# Relays.net
KiCad netlist of a schematic drawn in Altium Designer
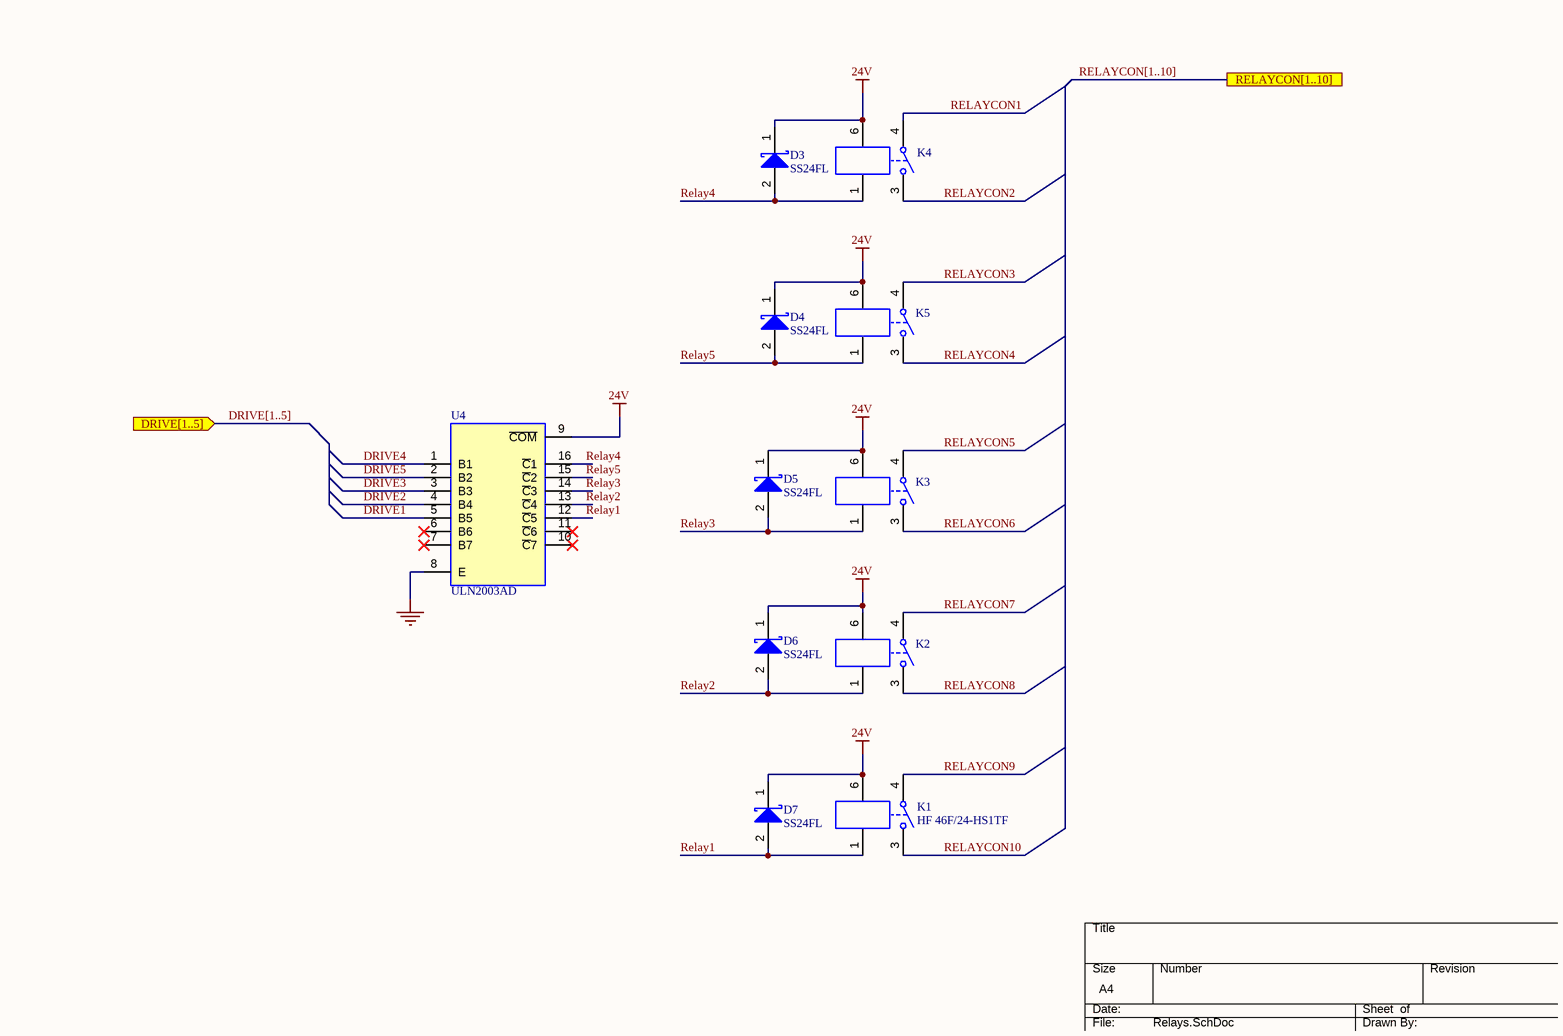
[diagram p0: Relays.SchDoc]

(export (version "E")
  (design (tool "Eeschema 10.0.6"))
  (components
    (comp (ref "D3")
      (value "SS24FL")
      (footprint "SOD-123F")
      (fields (field (name "PART NUMBER") "DIS-000000002"))
      (libsource (lib "CMA") (part "DSchottky"))
    )
    (comp (ref "D4")
      (value "SS24FL")
      (footprint "SOD-123F")
      (fields (field (name "PART NUMBER") "DIS-000000002"))
      (libsource (lib "CMA") (part "DSchottky"))
    )
    (comp (ref "D5")
      (value "SS24FL")
      (footprint "SOD-123F")
      (fields (field (name "PART NUMBER") "DIS-000000002"))
      (libsource (lib "CMA") (part "DSchottky"))
    )
    (comp (ref "D6")
      (value "SS24FL")
      (footprint "SOD-123F")
      (fields (field (name "PART NUMBER") "DIS-000000002"))
      (libsource (lib "CMA") (part "DSchottky"))
    )
    (comp (ref "D7")
      (value "SS24FL")
      (footprint "SOD-123F")
      (fields (field (name "PART NUMBER") "DIS-000000002"))
      (libsource (lib "CMA") (part "DSchottky"))
    )
    (comp (ref "K1")
      (value "HF 46F/24-HS1TF")
      (footprint "G6BU-1114P")
      (fields (field (name "PART NUMBER") "RLY-000000002"))
      (libsource (lib "CMA") (part "G6BU-1114P"))
    )
    (comp (ref "K2")
      (value "HF 46F/24-HS1TF")
      (footprint "G6BU-1114P")
      (fields (field (name "PART NUMBER") "RLY-000000002"))
      (libsource (lib "CMA") (part "G6BU-1114P"))
    )
    (comp (ref "K3")
      (value "HF 46F/24-HS1TF")
      (footprint "G6BU-1114P")
      (fields (field (name "PART NUMBER") "RLY-000000002"))
      (libsource (lib "CMA") (part "G6BU-1114P"))
    )
    (comp (ref "K4")
      (value "HF 46F/24-HS1TF")
      (footprint "G6BU-1114P")
      (fields (field (name "PART NUMBER") "RLY-000000002"))
      (libsource (lib "CMA") (part "G6BU-1114P"))
    )
    (comp (ref "K5")
      (value "HF 46F/24-HS1TF")
      (footprint "G6BU-1114P")
      (fields (field (name "PART NUMBER") "RLY-000000002"))
      (libsource (lib "CMA") (part "G6BU-1114P"))
    )
    (comp (ref "U4")
      (value "ULN2003AD")
      (footprint "SOIC-16")
      (fields (field (name "PART NUMBER") "ICD-000000003"))
      (libsource (lib "CMA") (part "ULN2003AD"))
    )
  )
  (nets
    (net (code "1") (name "/DRIVE1") (class "Default")
      (node (ref "U4") (pin "5") (pinfunction "B5_5") (pintype "passive"))
    )
    (net (code "2") (name "/DRIVE2") (class "Default")
      (node (ref "U4") (pin "4") (pinfunction "B4_4") (pintype "passive"))
    )
    (net (code "3") (name "/DRIVE3") (class "Default")
      (node (ref "U4") (pin "3") (pinfunction "B3_3") (pintype "passive"))
    )
    (net (code "4") (name "/DRIVE4") (class "Default")
      (node (ref "U4") (pin "1") (pinfunction "B1_1") (pintype "passive"))
    )
    (net (code "5") (name "/DRIVE5") (class "Default")
      (node (ref "U4") (pin "2") (pinfunction "B2_2") (pintype "passive"))
    )
    (net (code "7") (name "/RELAYCON1") (class "Default")
      (node (ref "K4") (pin "4") (pinfunction "4_4") (pintype "passive"))
    )
    (net (code "8") (name "/RELAYCON2") (class "Default")
      (node (ref "K4") (pin "3") (pinfunction "3_3") (pintype "passive"))
    )
    (net (code "9") (name "/RELAYCON3") (class "Default")
      (node (ref "K5") (pin "4") (pinfunction "4_4") (pintype "passive"))
    )
    (net (code "10") (name "/RELAYCON4") (class "Default")
      (node (ref "K5") (pin "3") (pinfunction "3_3") (pintype "passive"))
    )
    (net (code "11") (name "/RELAYCON5") (class "Default")
      (node (ref "K3") (pin "4") (pinfunction "4_4") (pintype "passive"))
    )
    (net (code "12") (name "/RELAYCON6") (class "Default")
      (node (ref "K3") (pin "3") (pinfunction "3_3") (pintype "passive"))
    )
    (net (code "13") (name "/RELAYCON7") (class "Default")
      (node (ref "K2") (pin "4") (pinfunction "4_4") (pintype "passive"))
    )
    (net (code "14") (name "/RELAYCON8") (class "Default")
      (node (ref "K2") (pin "3") (pinfunction "3_3") (pintype "passive"))
    )
    (net (code "15") (name "/RELAYCON9") (class "Default")
      (node (ref "K1") (pin "4") (pinfunction "4_4") (pintype "passive"))
    )
    (net (code "16") (name "/RELAYCON10") (class "Default")
      (node (ref "K1") (pin "3") (pinfunction "3_3") (pintype "passive"))
    )
    (net (code "18") (name "/Relay1") (class "Default")
      (node (ref "D7") (pin "2") (pinfunction "A_2") (pintype "passive"))
      (node (ref "K1") (pin "1") (pinfunction "1_1") (pintype "passive"))
      (node (ref "U4") (pin "12") (pinfunction "~{C}5_12") (pintype "open_collector"))
    )
    (net (code "19") (name "/Relay2") (class "Default")
      (node (ref "D6") (pin "2") (pinfunction "A_2") (pintype "passive"))
      (node (ref "K2") (pin "1") (pinfunction "1_1") (pintype "passive"))
      (node (ref "U4") (pin "13") (pinfunction "~{C}4_13") (pintype "open_collector"))
    )
    (net (code "20") (name "/Relay3") (class "Default")
      (node (ref "D5") (pin "2") (pinfunction "A_2") (pintype "passive"))
      (node (ref "K3") (pin "1") (pinfunction "1_1") (pintype "passive"))
      (node (ref "U4") (pin "14") (pinfunction "~{C}3_14") (pintype "open_collector"))
    )
    (net (code "21") (name "/Relay4") (class "Default")
      (node (ref "D3") (pin "2") (pinfunction "A_2") (pintype "passive"))
      (node (ref "K4") (pin "1") (pinfunction "1_1") (pintype "passive"))
      (node (ref "U4") (pin "16") (pinfunction "~{C}1_16") (pintype "open_collector"))
    )
    (net (code "22") (name "/Relay5") (class "Default")
      (node (ref "D4") (pin "2") (pinfunction "A_2") (pintype "passive"))
      (node (ref "K5") (pin "1") (pinfunction "1_1") (pintype "passive"))
      (node (ref "U4") (pin "15") (pinfunction "~{C}2_15") (pintype "open_collector"))
    )
    (net (code "23") (name "24V") (class "Default")
      (node (ref "D3") (pin "1") (pinfunction "K_1") (pintype "passive"))
      (node (ref "D4") (pin "1") (pinfunction "K_1") (pintype "passive"))
      (node (ref "D5") (pin "1") (pinfunction "K_1") (pintype "passive"))
      (node (ref "D6") (pin "1") (pinfunction "K_1") (pintype "passive"))
      (node (ref "D7") (pin "1") (pinfunction "K_1") (pintype "passive"))
      (node (ref "K1") (pin "6") (pinfunction "6_6") (pintype "passive"))
      (node (ref "K2") (pin "6") (pinfunction "6_6") (pintype "passive"))
      (node (ref "K3") (pin "6") (pinfunction "6_6") (pintype "passive"))
      (node (ref "K4") (pin "6") (pinfunction "6_6") (pintype "passive"))
      (node (ref "K5") (pin "6") (pinfunction "6_6") (pintype "passive"))
      (node (ref "U4") (pin "9") (pinfunction "~{COM}_9") (pintype "passive"))
    )
    (net (code "24") (name "GND") (class "Default")
      (node (ref "U4") (pin "8") (pinfunction "E_8") (pintype "power_in"))
    )
    (net (code "25") (name "unconnected-(U4-B6-Pad6)") (class "Default")
      (node (ref "U4") (pin "6") (pinfunction "B6_6") (pintype "passive+no_connect"))
    )
    (net (code "26") (name "unconnected-(U4-B7-Pad7)") (class "Default")
      (node (ref "U4") (pin "7") (pinfunction "B7_7") (pintype "passive+no_connect"))
    )
    (net (code "27") (name "unconnected-(U4-~{C}6-Pad11)") (class "Default")
      (node (ref "U4") (pin "11") (pinfunction "~{C}6_11") (pintype "open_collector+no_connect"))
    )
    (net (code "28") (name "unconnected-(U4-~{C}7-Pad10)") (class "Default")
      (node (ref "U4") (pin "10") (pinfunction "~{C}7_10") (pintype "open_collector+no_connect"))
    )
  )
)
